# Relays.net
KiCad netlist of a schematic drawn in Altium Designer
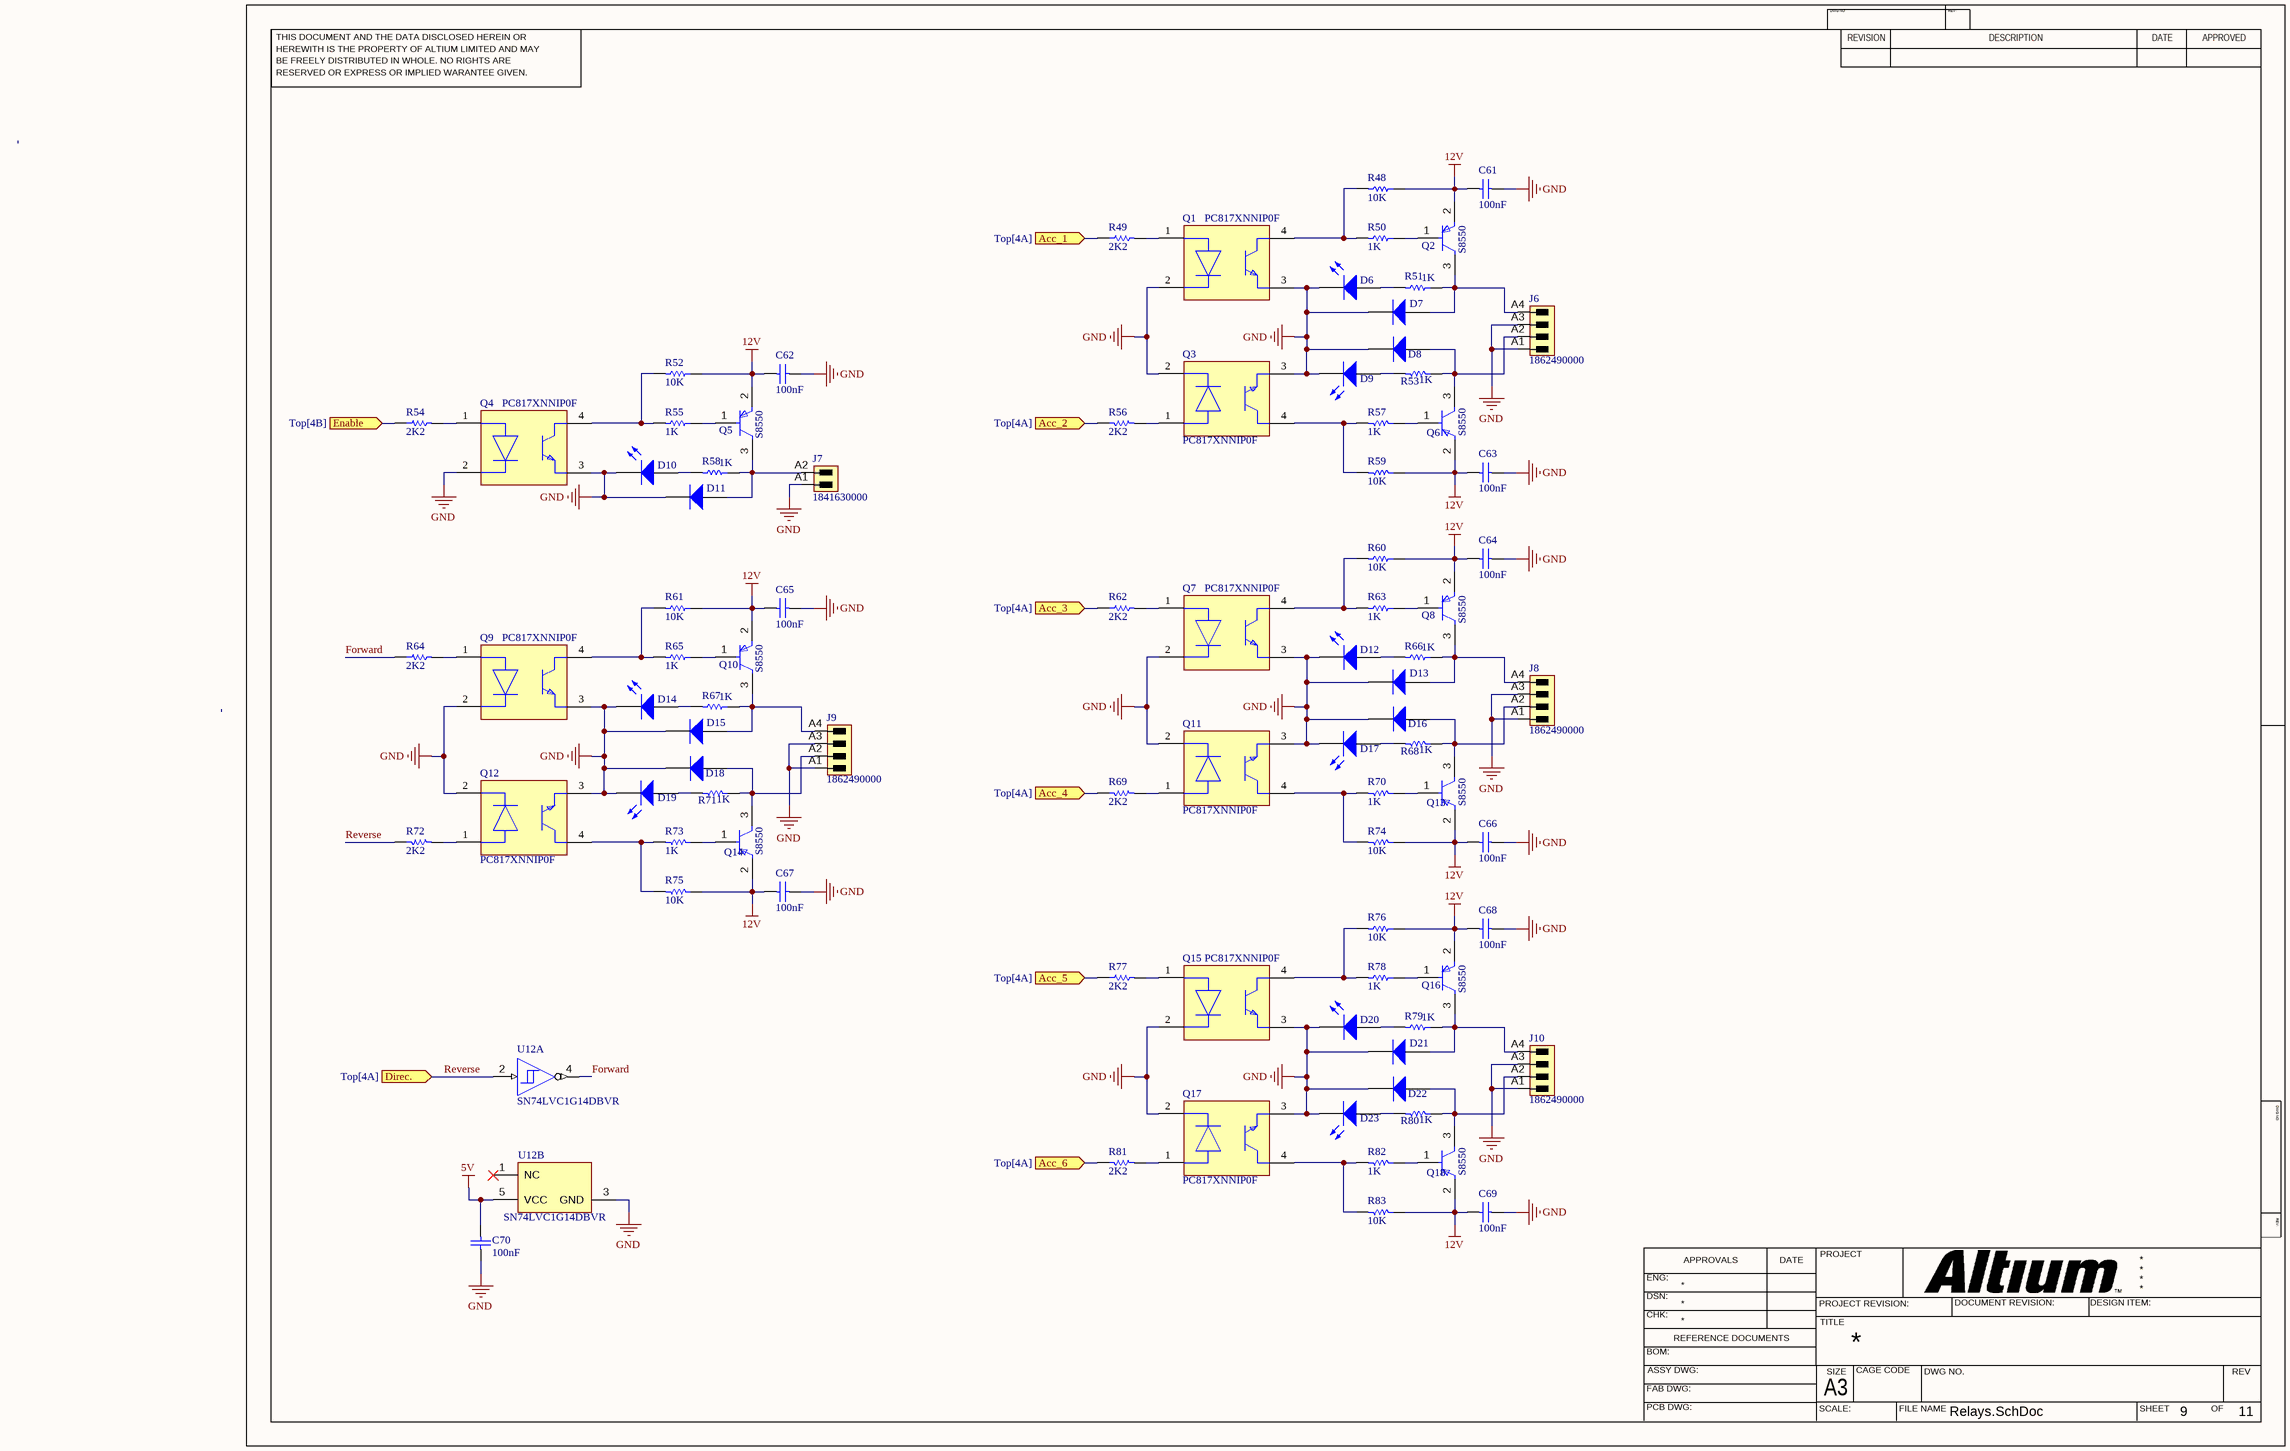
[diagram p0: Relays.SchDoc]

(export (version "E")
  (design (tool "Eeschema 10.0.6"))
  (components
    (comp (ref "C61")
      (value "100nF")
      (description "Capacitor")
      (libsource (lib "Simulation Generic Components") (part "Capacitor"))
    )
    (comp (ref "C62")
      (value "100nF")
      (description "Capacitor")
      (libsource (lib "Simulation Generic Components") (part "Capacitor"))
    )
    (comp (ref "C63")
      (value "100nF")
      (description "Capacitor")
      (libsource (lib "Simulation Generic Components") (part "Capacitor"))
    )
    (comp (ref "C64")
      (value "100nF")
      (description "Capacitor")
      (libsource (lib "Simulation Generic Components") (part "Capacitor"))
    )
    (comp (ref "C65")
      (value "100nF")
      (description "Capacitor")
      (libsource (lib "Simulation Generic Components") (part "Capacitor"))
    )
    (comp (ref "C66")
      (value "100nF")
      (description "Capacitor")
      (libsource (lib "Simulation Generic Components") (part "Capacitor"))
    )
    (comp (ref "C67")
      (value "100nF")
      (description "Capacitor")
      (libsource (lib "Simulation Generic Components") (part "Capacitor"))
    )
    (comp (ref "C68")
      (value "100nF")
      (description "Capacitor")
      (libsource (lib "Simulation Generic Components") (part "Capacitor"))
    )
    (comp (ref "C69")
      (value "100nF")
      (description "Capacitor")
      (libsource (lib "Simulation Generic Components") (part "Capacitor"))
    )
    (comp (ref "C70")
      (value "100nF")
      (description "Capacitor")
      (libsource (lib "Simulation Generic Components") (part "Capacitor"))
    )
    (comp (ref "D6")
      (value "Light-Emitting Diode")
      (libsource (lib "Simulation Generic Components") (part "LED"))
    )
    (comp (ref "D7") (value "Diode") (libsource (lib "Simulation Generic Components") (part "Diode")))
    (comp (ref "D8") (value "Diode") (libsource (lib "Simulation Generic Components") (part "Diode")))
    (comp (ref "D9")
      (value "Light-Emitting Diode")
      (libsource (lib "Simulation Generic Components") (part "LED"))
    )
    (comp (ref "D10")
      (value "Light-Emitting Diode")
      (libsource (lib "Simulation Generic Components") (part "LED"))
    )
    (comp (ref "D11") (value "Diode") (libsource (lib "Simulation Generic Components") (part "Diode")))
    (comp (ref "D12")
      (value "Light-Emitting Diode")
      (libsource (lib "Simulation Generic Components") (part "LED"))
    )
    (comp (ref "D13") (value "Diode") (libsource (lib "Simulation Generic Components") (part "Diode")))
    (comp (ref "D14")
      (value "Light-Emitting Diode")
      (libsource (lib "Simulation Generic Components") (part "LED"))
    )
    (comp (ref "D15") (value "Diode") (libsource (lib "Simulation Generic Components") (part "Diode")))
    (comp (ref "D16") (value "Diode") (libsource (lib "Simulation Generic Components") (part "Diode")))
    (comp (ref "D17")
      (value "Light-Emitting Diode")
      (libsource (lib "Simulation Generic Components") (part "LED"))
    )
    (comp (ref "D18") (value "Diode") (libsource (lib "Simulation Generic Components") (part "Diode")))
    (comp (ref "D19")
      (value "Light-Emitting Diode")
      (libsource (lib "Simulation Generic Components") (part "LED"))
    )
    (comp (ref "D20")
      (value "Light-Emitting Diode")
      (libsource (lib "Simulation Generic Components") (part "LED"))
    )
    (comp (ref "D21") (value "Diode") (libsource (lib "Simulation Generic Components") (part "Diode")))
    (comp (ref "D22") (value "Diode") (libsource (lib "Simulation Generic Components") (part "Diode")))
    (comp (ref "D23")
      (value "Light-Emitting Diode")
      (libsource (lib "Simulation Generic Components") (part "LED"))
    )
    (comp (ref "J6")
      (value "1862490000")
      (footprint "SC_SMT_3_81_90G_04")
      (description "OMNIMATE Signal - series BC/SC 3.81")
      (fields (field (name "MANUFACTURER") "Weidmueller"))
      (libsource (lib "Altium Content Vault") (part "Header_Male_04_1x04"))
    )
    (comp (ref "J7")
      (value "1841630000")
      (footprint "SL_SMT_3_5_90G_02")
      (description "OMNIMATE Signal - series BL/SL 3.50")
      (fields (field (name "MANUFACTURER") "Weidmueller"))
      (libsource (lib "Altium Content Vault") (part "Header_Male_02_1x02"))
    )
    (comp (ref "J8")
      (value "1862490000")
      (footprint "SC_SMT_3_81_90G_04")
      (description "OMNIMATE Signal - series BC/SC 3.81")
      (fields (field (name "MANUFACTURER") "Weidmueller"))
      (libsource (lib "Altium Content Vault") (part "Header_Male_04_1x04"))
    )
    (comp (ref "J9")
      (value "1862490000")
      (footprint "SC_SMT_3_81_90G_04")
      (description "OMNIMATE Signal - series BC/SC 3.81")
      (fields (field (name "MANUFACTURER") "Weidmueller"))
      (libsource (lib "Altium Content Vault") (part "Header_Male_04_1x04"))
    )
    (comp (ref "J10")
      (value "1862490000")
      (footprint "SC_SMT_3_81_90G_04")
      (description "OMNIMATE Signal - series BC/SC 3.81")
      (fields (field (name "MANUFACTURER") "Weidmueller"))
      (libsource (lib "Altium Content Vault") (part "Header_Male_04_1x04"))
    )
    (comp (ref "Q1")
      (value "PC817XNNIP0F")
      (footprint "FP-PC817XNNIP0F-MFG")
      (description "OPTOISOLATOR 5KV TRANS 4SMD")
      (libsource (lib "") (part "6470904bf6395c62928ee73e60120b8_1"))
    )
    (comp (ref "Q2")
      (value "S8550")
      (footprint "FP-SOT-23-IPC_B")
      (description "TRANS PNP 25V 1.5A SOT23")
      (libsource (lib "Altium Content Vault") (part "0e8486ed3b47d9c69b8404ba87cf0f7"))
    )
    (comp (ref "Q3")
      (value "PC817XNNIP0F")
      (footprint "FP-PC817XNNIP0F-MFG")
      (description "OPTOISOLATOR 5KV TRANS 4SMD")
      (libsource (lib "Altium Content Vault") (part "6470904bf6395c62928ee73e60120b8"))
    )
    (comp (ref "Q4")
      (value "PC817XNNIP0F")
      (footprint "FP-PC817XNNIP0F-MFG")
      (description "OPTOISOLATOR 5KV TRANS 4SMD")
      (libsource (lib "") (part "6470904bf6395c62928ee73e60120b8_1"))
    )
    (comp (ref "Q5")
      (value "S8550")
      (footprint "FP-SOT-23-IPC_B")
      (description "TRANS PNP 25V 1.5A SOT23")
      (libsource (lib "Altium Content Vault") (part "0e8486ed3b47d9c69b8404ba87cf0f7"))
    )
    (comp (ref "Q6")
      (value "S8550")
      (footprint "FP-SOT-23-IPC_B")
      (description "TRANS PNP 25V 1.5A SOT23")
      (libsource (lib "Altium Content Vault") (part "0e8486ed3b47d9c69b8404ba87cf0f7"))
    )
    (comp (ref "Q7")
      (value "PC817XNNIP0F")
      (footprint "FP-PC817XNNIP0F-MFG")
      (description "OPTOISOLATOR 5KV TRANS 4SMD")
      (libsource (lib "") (part "6470904bf6395c62928ee73e60120b8_1"))
    )
    (comp (ref "Q8")
      (value "S8550")
      (footprint "FP-SOT-23-IPC_B")
      (description "TRANS PNP 25V 1.5A SOT23")
      (libsource (lib "Altium Content Vault") (part "0e8486ed3b47d9c69b8404ba87cf0f7"))
    )
    (comp (ref "Q9")
      (value "PC817XNNIP0F")
      (footprint "FP-PC817XNNIP0F-MFG")
      (description "OPTOISOLATOR 5KV TRANS 4SMD")
      (libsource (lib "") (part "6470904bf6395c62928ee73e60120b8_1"))
    )
    (comp (ref "Q10")
      (value "S8550")
      (footprint "FP-SOT-23-IPC_B")
      (description "TRANS PNP 25V 1.5A SOT23")
      (libsource (lib "Altium Content Vault") (part "0e8486ed3b47d9c69b8404ba87cf0f7"))
    )
    (comp (ref "Q11")
      (value "PC817XNNIP0F")
      (footprint "FP-PC817XNNIP0F-MFG")
      (description "OPTOISOLATOR 5KV TRANS 4SMD")
      (libsource (lib "Altium Content Vault") (part "6470904bf6395c62928ee73e60120b8"))
    )
    (comp (ref "Q12")
      (value "PC817XNNIP0F")
      (footprint "FP-PC817XNNIP0F-MFG")
      (description "OPTOISOLATOR 5KV TRANS 4SMD")
      (libsource (lib "Altium Content Vault") (part "6470904bf6395c62928ee73e60120b8"))
    )
    (comp (ref "Q13")
      (value "S8550")
      (footprint "FP-SOT-23-IPC_B")
      (description "TRANS PNP 25V 1.5A SOT23")
      (libsource (lib "Altium Content Vault") (part "0e8486ed3b47d9c69b8404ba87cf0f7"))
    )
    (comp (ref "Q14")
      (value "S8550")
      (footprint "FP-SOT-23-IPC_B")
      (description "TRANS PNP 25V 1.5A SOT23")
      (libsource (lib "Altium Content Vault") (part "0e8486ed3b47d9c69b8404ba87cf0f7"))
    )
    (comp (ref "Q15")
      (value "PC817XNNIP0F")
      (footprint "FP-PC817XNNIP0F-MFG")
      (description "OPTOISOLATOR 5KV TRANS 4SMD")
      (libsource (lib "") (part "6470904bf6395c62928ee73e60120b8_1"))
    )
    (comp (ref "Q16")
      (value "S8550")
      (footprint "FP-SOT-23-IPC_B")
      (description "TRANS PNP 25V 1.5A SOT23")
      (libsource (lib "Altium Content Vault") (part "0e8486ed3b47d9c69b8404ba87cf0f7"))
    )
    (comp (ref "Q17")
      (value "PC817XNNIP0F")
      (footprint "FP-PC817XNNIP0F-MFG")
      (description "OPTOISOLATOR 5KV TRANS 4SMD")
      (libsource (lib "Altium Content Vault") (part "6470904bf6395c62928ee73e60120b8"))
    )
    (comp (ref "Q18")
      (value "S8550")
      (footprint "FP-SOT-23-IPC_B")
      (description "TRANS PNP 25V 1.5A SOT23")
      (libsource (lib "Altium Content Vault") (part "0e8486ed3b47d9c69b8404ba87cf0f7"))
    )
    (comp (ref "R48")
      (value "10K")
      (description "Resistor")
      (libsource (lib "Simulation Generic Components") (part "Resistor"))
    )
    (comp (ref "R49")
      (value "2K2")
      (description "Resistor")
      (libsource (lib "Simulation Generic Components") (part "Resistor"))
    )
    (comp (ref "R50")
      (value "1K")
      (description "Resistor")
      (libsource (lib "Simulation Generic Components") (part "Resistor"))
    )
    (comp (ref "R51")
      (value "1K")
      (description "Resistor")
      (libsource (lib "Simulation Generic Components") (part "Resistor"))
    )
    (comp (ref "R52")
      (value "10K")
      (description "Resistor")
      (libsource (lib "Simulation Generic Components") (part "Resistor"))
    )
    (comp (ref "R53")
      (value "1K")
      (description "Resistor")
      (libsource (lib "Simulation Generic Components") (part "Resistor"))
    )
    (comp (ref "R54")
      (value "2K2")
      (description "Resistor")
      (libsource (lib "Simulation Generic Components") (part "Resistor"))
    )
    (comp (ref "R55")
      (value "1K")
      (description "Resistor")
      (libsource (lib "Simulation Generic Components") (part "Resistor"))
    )
    (comp (ref "R56")
      (value "2K2")
      (description "Resistor")
      (libsource (lib "Simulation Generic Components") (part "Resistor"))
    )
    (comp (ref "R57")
      (value "1K")
      (description "Resistor")
      (libsource (lib "Simulation Generic Components") (part "Resistor"))
    )
    (comp (ref "R58")
      (value "1K")
      (description "Resistor")
      (libsource (lib "Simulation Generic Components") (part "Resistor"))
    )
    (comp (ref "R59")
      (value "10K")
      (description "Resistor")
      (libsource (lib "Simulation Generic Components") (part "Resistor"))
    )
    (comp (ref "R60")
      (value "10K")
      (description "Resistor")
      (libsource (lib "Simulation Generic Components") (part "Resistor"))
    )
    (comp (ref "R61")
      (value "10K")
      (description "Resistor")
      (libsource (lib "Simulation Generic Components") (part "Resistor"))
    )
    (comp (ref "R62")
      (value "2K2")
      (description "Resistor")
      (libsource (lib "Simulation Generic Components") (part "Resistor"))
    )
    (comp (ref "R63")
      (value "1K")
      (description "Resistor")
      (libsource (lib "Simulation Generic Components") (part "Resistor"))
    )
    (comp (ref "R64")
      (value "2K2")
      (description "Resistor")
      (libsource (lib "Simulation Generic Components") (part "Resistor"))
    )
    (comp (ref "R65")
      (value "1K")
      (description "Resistor")
      (libsource (lib "Simulation Generic Components") (part "Resistor"))
    )
    (comp (ref "R66")
      (value "1K")
      (description "Resistor")
      (libsource (lib "Simulation Generic Components") (part "Resistor"))
    )
    (comp (ref "R67")
      (value "1K")
      (description "Resistor")
      (libsource (lib "Simulation Generic Components") (part "Resistor"))
    )
    (comp (ref "R68")
      (value "1K")
      (description "Resistor")
      (libsource (lib "Simulation Generic Components") (part "Resistor"))
    )
    (comp (ref "R69")
      (value "2K2")
      (description "Resistor")
      (libsource (lib "Simulation Generic Components") (part "Resistor"))
    )
    (comp (ref "R70")
      (value "1K")
      (description "Resistor")
      (libsource (lib "Simulation Generic Components") (part "Resistor"))
    )
    (comp (ref "R71")
      (value "1K")
      (description "Resistor")
      (libsource (lib "Simulation Generic Components") (part "Resistor"))
    )
    (comp (ref "R72")
      (value "2K2")
      (description "Resistor")
      (libsource (lib "Simulation Generic Components") (part "Resistor"))
    )
    (comp (ref "R73")
      (value "1K")
      (description "Resistor")
      (libsource (lib "Simulation Generic Components") (part "Resistor"))
    )
    (comp (ref "R74")
      (value "10K")
      (description "Resistor")
      (libsource (lib "Simulation Generic Components") (part "Resistor"))
    )
    (comp (ref "R75")
      (value "10K")
      (description "Resistor")
      (libsource (lib "Simulation Generic Components") (part "Resistor"))
    )
    (comp (ref "R76")
      (value "10K")
      (description "Resistor")
      (libsource (lib "Simulation Generic Components") (part "Resistor"))
    )
    (comp (ref "R77")
      (value "2K2")
      (description "Resistor")
      (libsource (lib "Simulation Generic Components") (part "Resistor"))
    )
    (comp (ref "R78")
      (value "1K")
      (description "Resistor")
      (libsource (lib "Simulation Generic Components") (part "Resistor"))
    )
    (comp (ref "R79")
      (value "1K")
      (description "Resistor")
      (libsource (lib "Simulation Generic Components") (part "Resistor"))
    )
    (comp (ref "R80")
      (value "1K")
      (description "Resistor")
      (libsource (lib "Simulation Generic Components") (part "Resistor"))
    )
    (comp (ref "R81")
      (value "2K2")
      (description "Resistor")
      (libsource (lib "Simulation Generic Components") (part "Resistor"))
    )
    (comp (ref "R82")
      (value "1K")
      (description "Resistor")
      (libsource (lib "Simulation Generic Components") (part "Resistor"))
    )
    (comp (ref "R83")
      (value "10K")
      (description "Resistor")
      (libsource (lib "Simulation Generic Components") (part "Resistor"))
    )
    (comp (ref "U12")
      (value "SN74LVC1G14DBVR")
      (footprint "DBV0005A_L")
      (description "Single Schmitt-Trigger Inverter, DBV0005A, LARGE T&R")
      (fields
        (field (name "GENERIC PART NUMBER") "SN74LVC1G14")
        (field (name "MANUFACTURER") "Texas Instruments")
      )
      (libsource (lib "Altium Content Vault") (part "TI-SN74XXX1XX4-XX-5-SCHMITT"))
    )
  )
  (nets
    (net (code "1") (name "/Acc_1") (class "Default")
      (node (ref "R49") (pin "1") (pinfunction "1_1") (pintype "passive"))
    )
    (net (code "2") (name "/Acc_2") (class "Default")
      (node (ref "R56") (pin "1") (pinfunction "1_1") (pintype "passive"))
    )
    (net (code "3") (name "/Acc_3") (class "Default")
      (node (ref "R62") (pin "1") (pinfunction "1_1") (pintype "passive"))
    )
    (net (code "4") (name "/Acc_4") (class "Default")
      (node (ref "R69") (pin "1") (pinfunction "1_1") (pintype "passive"))
    )
    (net (code "5") (name "/Acc_5") (class "Default")
      (node (ref "R77") (pin "1") (pinfunction "1_1") (pintype "passive"))
    )
    (net (code "6") (name "/Acc_6") (class "Default")
      (node (ref "R81") (pin "1") (pinfunction "1_1") (pintype "passive"))
    )
    (net (code "7") (name "/Enable") (class "Default")
      (node (ref "R54") (pin "1") (pinfunction "1_1") (pintype "passive"))
    )
    (net (code "8") (name "/Forward") (class "Default")
      (node (ref "R64") (pin "1") (pinfunction "1_1") (pintype "passive"))
      (node (ref "U12") (pin "4") (pinfunction "Y_4") (pintype "output"))
    )
    (net (code "9") (name "/Reverse") (class "Default")
      (node (ref "R72") (pin "1") (pinfunction "1_1") (pintype "passive"))
      (node (ref "U12") (pin "2") (pinfunction "A_2") (pintype "input"))
    )
    (net (code "10") (name "5V") (class "Default")
      (node (ref "C70") (pin "1") (pinfunction "1_1") (pintype "passive"))
      (node (ref "U12") (pin "5") (pinfunction "VCC_5") (pintype "power_in"))
    )
    (net (code "11") (name "12V") (class "Default")
      (node (ref "C61") (pin "1") (pinfunction "1_1") (pintype "passive"))
      (node (ref "C62") (pin "1") (pinfunction "1_1") (pintype "passive"))
      (node (ref "C63") (pin "1") (pinfunction "1_1") (pintype "passive"))
      (node (ref "C64") (pin "1") (pinfunction "1_1") (pintype "passive"))
      (node (ref "C65") (pin "1") (pinfunction "1_1") (pintype "passive"))
      (node (ref "C66") (pin "1") (pinfunction "1_1") (pintype "passive"))
      (node (ref "C67") (pin "1") (pinfunction "1_1") (pintype "passive"))
      (node (ref "C68") (pin "1") (pinfunction "1_1") (pintype "passive"))
      (node (ref "C69") (pin "1") (pinfunction "1_1") (pintype "passive"))
      (node (ref "Q10") (pin "2") (pinfunction "E_2") (pintype "passive"))
      (node (ref "Q13") (pin "2") (pinfunction "E_2") (pintype "passive"))
      (node (ref "Q14") (pin "2") (pinfunction "E_2") (pintype "passive"))
      (node (ref "Q16") (pin "2") (pinfunction "E_2") (pintype "passive"))
      (node (ref "Q18") (pin "2") (pinfunction "E_2") (pintype "passive"))
      (node (ref "Q2") (pin "2") (pinfunction "E_2") (pintype "passive"))
      (node (ref "Q5") (pin "2") (pinfunction "E_2") (pintype "passive"))
      (node (ref "Q6") (pin "2") (pinfunction "E_2") (pintype "passive"))
      (node (ref "Q8") (pin "2") (pinfunction "E_2") (pintype "passive"))
      (node (ref "R48") (pin "1") (pinfunction "1_1") (pintype "passive"))
      (node (ref "R52") (pin "1") (pinfunction "1_1") (pintype "passive"))
      (node (ref "R59") (pin "1") (pinfunction "1_1") (pintype "passive"))
      (node (ref "R60") (pin "1") (pinfunction "1_1") (pintype "passive"))
      (node (ref "R61") (pin "1") (pinfunction "1_1") (pintype "passive"))
      (node (ref "R74") (pin "1") (pinfunction "1_1") (pintype "passive"))
      (node (ref "R75") (pin "1") (pinfunction "1_1") (pintype "passive"))
      (node (ref "R76") (pin "1") (pinfunction "1_1") (pintype "passive"))
      (node (ref "R83") (pin "1") (pinfunction "1_1") (pintype "passive"))
    )
    (net (code "12") (name "GND") (class "Default")
      (node (ref "C61") (pin "2") (pinfunction "2_2") (pintype "passive"))
      (node (ref "C62") (pin "2") (pinfunction "2_2") (pintype "passive"))
      (node (ref "C63") (pin "2") (pinfunction "2_2") (pintype "passive"))
      (node (ref "C64") (pin "2") (pinfunction "2_2") (pintype "passive"))
      (node (ref "C65") (pin "2") (pinfunction "2_2") (pintype "passive"))
      (node (ref "C66") (pin "2") (pinfunction "2_2") (pintype "passive"))
      (node (ref "C67") (pin "2") (pinfunction "2_2") (pintype "passive"))
      (node (ref "C68") (pin "2") (pinfunction "2_2") (pintype "passive"))
      (node (ref "C69") (pin "2") (pinfunction "2_2") (pintype "passive"))
      (node (ref "C70") (pin "2") (pinfunction "2_2") (pintype "passive"))
      (node (ref "D10") (pin "2") (pinfunction "K_2") (pintype "passive"))
      (node (ref "D11") (pin "2") (pinfunction "K_2") (pintype "passive"))
      (node (ref "D12") (pin "2") (pinfunction "K_2") (pintype "passive"))
      (node (ref "D13") (pin "2") (pinfunction "K_2") (pintype "passive"))
      (node (ref "D14") (pin "2") (pinfunction "K_2") (pintype "passive"))
      (node (ref "D15") (pin "2") (pinfunction "K_2") (pintype "passive"))
      (node (ref "D16") (pin "2") (pinfunction "K_2") (pintype "passive"))
      (node (ref "D17") (pin "2") (pinfunction "K_2") (pintype "passive"))
      (node (ref "D18") (pin "2") (pinfunction "K_2") (pintype "passive"))
      (node (ref "D19") (pin "2") (pinfunction "K_2") (pintype "passive"))
      (node (ref "D20") (pin "2") (pinfunction "K_2") (pintype "passive"))
      (node (ref "D21") (pin "2") (pinfunction "K_2") (pintype "passive"))
      (node (ref "D22") (pin "2") (pinfunction "K_2") (pintype "passive"))
      (node (ref "D23") (pin "2") (pinfunction "K_2") (pintype "passive"))
      (node (ref "D6") (pin "2") (pinfunction "K_2") (pintype "passive"))
      (node (ref "D7") (pin "2") (pinfunction "K_2") (pintype "passive"))
      (node (ref "D8") (pin "2") (pinfunction "K_2") (pintype "passive"))
      (node (ref "D9") (pin "2") (pinfunction "K_2") (pintype "passive"))
      (node (ref "J10") (pin "A1") (pinfunction "A1_A1") (pintype "passive"))
      (node (ref "J10") (pin "A3") (pinfunction "A3_A3") (pintype "passive"))
      (node (ref "J6") (pin "A1") (pinfunction "A1_A1") (pintype "passive"))
      (node (ref "J6") (pin "A3") (pinfunction "A3_A3") (pintype "passive"))
      (node (ref "J7") (pin "A1") (pinfunction "A1_A1") (pintype "passive"))
      (node (ref "J8") (pin "A1") (pinfunction "A1_A1") (pintype "passive"))
      (node (ref "J8") (pin "A3") (pinfunction "A3_A3") (pintype "passive"))
      (node (ref "J9") (pin "A1") (pinfunction "A1_A1") (pintype "passive"))
      (node (ref "J9") (pin "A3") (pinfunction "A3_A3") (pintype "passive"))
      (node (ref "Q1") (pin "2") (pinfunction "C_2") (pintype "passive"))
      (node (ref "Q1") (pin "3") (pinfunction "E_3") (pintype "passive"))
      (node (ref "Q11") (pin "2") (pinfunction "C_2") (pintype "passive"))
      (node (ref "Q11") (pin "3") (pinfunction "E_3") (pintype "passive"))
      (node (ref "Q12") (pin "2") (pinfunction "C_2") (pintype "passive"))
      (node (ref "Q12") (pin "3") (pinfunction "E_3") (pintype "passive"))
      (node (ref "Q15") (pin "2") (pinfunction "C_2") (pintype "passive"))
      (node (ref "Q15") (pin "3") (pinfunction "E_3") (pintype "passive"))
      (node (ref "Q17") (pin "2") (pinfunction "C_2") (pintype "passive"))
      (node (ref "Q17") (pin "3") (pinfunction "E_3") (pintype "passive"))
      (node (ref "Q3") (pin "2") (pinfunction "C_2") (pintype "passive"))
      (node (ref "Q3") (pin "3") (pinfunction "E_3") (pintype "passive"))
      (node (ref "Q4") (pin "2") (pinfunction "C_2") (pintype "passive"))
      (node (ref "Q4") (pin "3") (pinfunction "E_3") (pintype "passive"))
      (node (ref "Q7") (pin "2") (pinfunction "C_2") (pintype "passive"))
      (node (ref "Q7") (pin "3") (pinfunction "E_3") (pintype "passive"))
      (node (ref "Q9") (pin "2") (pinfunction "C_2") (pintype "passive"))
      (node (ref "Q9") (pin "3") (pinfunction "E_3") (pintype "passive"))
      (node (ref "U12") (pin "3") (pinfunction "GND_3") (pintype "power_in"))
    )
    (net (code "13") (name "Net-(D6-A)") (class "Default")
      (node (ref "D6") (pin "1") (pinfunction "A_1") (pintype "passive"))
      (node (ref "R51") (pin "2") (pinfunction "2_2") (pintype "passive"))
    )
    (net (code "14") (name "Net-(D7-A)") (class "Default")
      (node (ref "D7") (pin "1") (pinfunction "A_1") (pintype "passive"))
      (node (ref "J6") (pin "A4") (pinfunction "A4_A4") (pintype "passive"))
      (node (ref "Q2") (pin "3") (pinfunction "C_3") (pintype "passive"))
      (node (ref "R51") (pin "1") (pinfunction "1_1") (pintype "passive"))
    )
    (net (code "15") (name "Net-(D8-A)") (class "Default")
      (node (ref "D8") (pin "1") (pinfunction "A_1") (pintype "passive"))
      (node (ref "J6") (pin "A2") (pinfunction "A2_A2") (pintype "passive"))
      (node (ref "Q6") (pin "3") (pinfunction "C_3") (pintype "passive"))
      (node (ref "R53") (pin "1") (pinfunction "1_1") (pintype "passive"))
    )
    (net (code "16") (name "Net-(D9-A)") (class "Default")
      (node (ref "D9") (pin "1") (pinfunction "A_1") (pintype "passive"))
      (node (ref "R53") (pin "2") (pinfunction "2_2") (pintype "passive"))
    )
    (net (code "17") (name "Net-(D10-A)") (class "Default")
      (node (ref "D10") (pin "1") (pinfunction "A_1") (pintype "passive"))
      (node (ref "R58") (pin "2") (pinfunction "2_2") (pintype "passive"))
    )
    (net (code "18") (name "Net-(D11-A)") (class "Default")
      (node (ref "D11") (pin "1") (pinfunction "A_1") (pintype "passive"))
      (node (ref "J7") (pin "A2") (pinfunction "A2_A2") (pintype "passive"))
      (node (ref "Q5") (pin "3") (pinfunction "C_3") (pintype "passive"))
      (node (ref "R58") (pin "1") (pinfunction "1_1") (pintype "passive"))
    )
    (net (code "19") (name "Net-(D12-A)") (class "Default")
      (node (ref "D12") (pin "1") (pinfunction "A_1") (pintype "passive"))
      (node (ref "R66") (pin "2") (pinfunction "2_2") (pintype "passive"))
    )
    (net (code "20") (name "Net-(D13-A)") (class "Default")
      (node (ref "D13") (pin "1") (pinfunction "A_1") (pintype "passive"))
      (node (ref "J8") (pin "A4") (pinfunction "A4_A4") (pintype "passive"))
      (node (ref "Q8") (pin "3") (pinfunction "C_3") (pintype "passive"))
      (node (ref "R66") (pin "1") (pinfunction "1_1") (pintype "passive"))
    )
    (net (code "21") (name "Net-(D14-A)") (class "Default")
      (node (ref "D14") (pin "1") (pinfunction "A_1") (pintype "passive"))
      (node (ref "R67") (pin "2") (pinfunction "2_2") (pintype "passive"))
    )
    (net (code "22") (name "Net-(D15-A)") (class "Default")
      (node (ref "D15") (pin "1") (pinfunction "A_1") (pintype "passive"))
      (node (ref "J9") (pin "A4") (pinfunction "A4_A4") (pintype "passive"))
      (node (ref "Q10") (pin "3") (pinfunction "C_3") (pintype "passive"))
      (node (ref "R67") (pin "1") (pinfunction "1_1") (pintype "passive"))
    )
    (net (code "23") (name "Net-(D16-A)") (class "Default")
      (node (ref "D16") (pin "1") (pinfunction "A_1") (pintype "passive"))
      (node (ref "J8") (pin "A2") (pinfunction "A2_A2") (pintype "passive"))
      (node (ref "Q13") (pin "3") (pinfunction "C_3") (pintype "passive"))
      (node (ref "R68") (pin "1") (pinfunction "1_1") (pintype "passive"))
    )
    (net (code "24") (name "Net-(D17-A)") (class "Default")
      (node (ref "D17") (pin "1") (pinfunction "A_1") (pintype "passive"))
      (node (ref "R68") (pin "2") (pinfunction "2_2") (pintype "passive"))
    )
    (net (code "25") (name "Net-(D18-A)") (class "Default")
      (node (ref "D18") (pin "1") (pinfunction "A_1") (pintype "passive"))
      (node (ref "J9") (pin "A2") (pinfunction "A2_A2") (pintype "passive"))
      (node (ref "Q14") (pin "3") (pinfunction "C_3") (pintype "passive"))
      (node (ref "R71") (pin "1") (pinfunction "1_1") (pintype "passive"))
    )
    (net (code "26") (name "Net-(D19-A)") (class "Default")
      (node (ref "D19") (pin "1") (pinfunction "A_1") (pintype "passive"))
      (node (ref "R71") (pin "2") (pinfunction "2_2") (pintype "passive"))
    )
    (net (code "27") (name "Net-(D20-A)") (class "Default")
      (node (ref "D20") (pin "1") (pinfunction "A_1") (pintype "passive"))
      (node (ref "R79") (pin "2") (pinfunction "2_2") (pintype "passive"))
    )
    (net (code "28") (name "Net-(D21-A)") (class "Default")
      (node (ref "D21") (pin "1") (pinfunction "A_1") (pintype "passive"))
      (node (ref "J10") (pin "A4") (pinfunction "A4_A4") (pintype "passive"))
      (node (ref "Q16") (pin "3") (pinfunction "C_3") (pintype "passive"))
      (node (ref "R79") (pin "1") (pinfunction "1_1") (pintype "passive"))
    )
    (net (code "29") (name "Net-(D22-A)") (class "Default")
      (node (ref "D22") (pin "1") (pinfunction "A_1") (pintype "passive"))
      (node (ref "J10") (pin "A2") (pinfunction "A2_A2") (pintype "passive"))
      (node (ref "Q18") (pin "3") (pinfunction "C_3") (pintype "passive"))
      (node (ref "R80") (pin "1") (pinfunction "1_1") (pintype "passive"))
    )
    (net (code "30") (name "Net-(D23-A)") (class "Default")
      (node (ref "D23") (pin "1") (pinfunction "A_1") (pintype "passive"))
      (node (ref "R80") (pin "2") (pinfunction "2_2") (pintype "passive"))
    )
    (net (code "31") (name "Net-(Q1-A)") (class "Default")
      (node (ref "Q1") (pin "1") (pinfunction "A_1") (pintype "passive"))
      (node (ref "R49") (pin "2") (pinfunction "2_2") (pintype "passive"))
    )
    (net (code "32") (name "Net-(Q1-C-Pad4)") (class "Default")
      (node (ref "Q1") (pin "4") (pinfunction "C_4") (pintype "passive"))
      (node (ref "R48") (pin "2") (pinfunction "2_2") (pintype "passive"))
      (node (ref "R50") (pin "2") (pinfunction "2_2") (pintype "passive"))
    )
    (net (code "33") (name "Net-(Q2-B)") (class "Default")
      (node (ref "Q2") (pin "1") (pinfunction "B_1") (pintype "passive"))
      (node (ref "R50") (pin "1") (pinfunction "1_1") (pintype "passive"))
    )
    (net (code "34") (name "Net-(Q3-A)") (class "Default")
      (node (ref "Q3") (pin "1") (pinfunction "A_1") (pintype "passive"))
      (node (ref "R56") (pin "2") (pinfunction "2_2") (pintype "passive"))
    )
    (net (code "35") (name "Net-(Q3-C-Pad4)") (class "Default")
      (node (ref "Q3") (pin "4") (pinfunction "C_4") (pintype "passive"))
      (node (ref "R57") (pin "2") (pinfunction "2_2") (pintype "passive"))
      (node (ref "R59") (pin "2") (pinfunction "2_2") (pintype "passive"))
    )
    (net (code "36") (name "Net-(Q4-A)") (class "Default")
      (node (ref "Q4") (pin "1") (pinfunction "A_1") (pintype "passive"))
      (node (ref "R54") (pin "2") (pinfunction "2_2") (pintype "passive"))
    )
    (net (code "37") (name "Net-(Q4-C-Pad4)") (class "Default")
      (node (ref "Q4") (pin "4") (pinfunction "C_4") (pintype "passive"))
      (node (ref "R52") (pin "2") (pinfunction "2_2") (pintype "passive"))
      (node (ref "R55") (pin "2") (pinfunction "2_2") (pintype "passive"))
    )
    (net (code "38") (name "Net-(Q5-B)") (class "Default")
      (node (ref "Q5") (pin "1") (pinfunction "B_1") (pintype "passive"))
      (node (ref "R55") (pin "1") (pinfunction "1_1") (pintype "passive"))
    )
    (net (code "39") (name "Net-(Q6-B)") (class "Default")
      (node (ref "Q6") (pin "1") (pinfunction "B_1") (pintype "passive"))
      (node (ref "R57") (pin "1") (pinfunction "1_1") (pintype "passive"))
    )
    (net (code "40") (name "Net-(Q7-A)") (class "Default")
      (node (ref "Q7") (pin "1") (pinfunction "A_1") (pintype "passive"))
      (node (ref "R62") (pin "2") (pinfunction "2_2") (pintype "passive"))
    )
    (net (code "41") (name "Net-(Q7-C-Pad4)") (class "Default")
      (node (ref "Q7") (pin "4") (pinfunction "C_4") (pintype "passive"))
      (node (ref "R60") (pin "2") (pinfunction "2_2") (pintype "passive"))
      (node (ref "R63") (pin "2") (pinfunction "2_2") (pintype "passive"))
    )
    (net (code "42") (name "Net-(Q8-B)") (class "Default")
      (node (ref "Q8") (pin "1") (pinfunction "B_1") (pintype "passive"))
      (node (ref "R63") (pin "1") (pinfunction "1_1") (pintype "passive"))
    )
    (net (code "43") (name "Net-(Q9-A)") (class "Default")
      (node (ref "Q9") (pin "1") (pinfunction "A_1") (pintype "passive"))
      (node (ref "R64") (pin "2") (pinfunction "2_2") (pintype "passive"))
    )
    (net (code "44") (name "Net-(Q9-C-Pad4)") (class "Default")
      (node (ref "Q9") (pin "4") (pinfunction "C_4") (pintype "passive"))
      (node (ref "R61") (pin "2") (pinfunction "2_2") (pintype "passive"))
      (node (ref "R65") (pin "2") (pinfunction "2_2") (pintype "passive"))
    )
    (net (code "45") (name "Net-(Q10-B)") (class "Default")
      (node (ref "Q10") (pin "1") (pinfunction "B_1") (pintype "passive"))
      (node (ref "R65") (pin "1") (pinfunction "1_1") (pintype "passive"))
    )
    (net (code "46") (name "Net-(Q11-A)") (class "Default")
      (node (ref "Q11") (pin "1") (pinfunction "A_1") (pintype "passive"))
      (node (ref "R69") (pin "2") (pinfunction "2_2") (pintype "passive"))
    )
    (net (code "47") (name "Net-(Q11-C-Pad4)") (class "Default")
      (node (ref "Q11") (pin "4") (pinfunction "C_4") (pintype "passive"))
      (node (ref "R70") (pin "2") (pinfunction "2_2") (pintype "passive"))
      (node (ref "R74") (pin "2") (pinfunction "2_2") (pintype "passive"))
    )
    (net (code "48") (name "Net-(Q12-A)") (class "Default")
      (node (ref "Q12") (pin "1") (pinfunction "A_1") (pintype "passive"))
      (node (ref "R72") (pin "2") (pinfunction "2_2") (pintype "passive"))
    )
    (net (code "49") (name "Net-(Q12-C-Pad4)") (class "Default")
      (node (ref "Q12") (pin "4") (pinfunction "C_4") (pintype "passive"))
      (node (ref "R73") (pin "2") (pinfunction "2_2") (pintype "passive"))
      (node (ref "R75") (pin "2") (pinfunction "2_2") (pintype "passive"))
    )
    (net (code "50") (name "Net-(Q13-B)") (class "Default")
      (node (ref "Q13") (pin "1") (pinfunction "B_1") (pintype "passive"))
      (node (ref "R70") (pin "1") (pinfunction "1_1") (pintype "passive"))
    )
    (net (code "51") (name "Net-(Q14-B)") (class "Default")
      (node (ref "Q14") (pin "1") (pinfunction "B_1") (pintype "passive"))
      (node (ref "R73") (pin "1") (pinfunction "1_1") (pintype "passive"))
    )
    (net (code "52") (name "Net-(Q15-A)") (class "Default")
      (node (ref "Q15") (pin "1") (pinfunction "A_1") (pintype "passive"))
      (node (ref "R77") (pin "2") (pinfunction "2_2") (pintype "passive"))
    )
    (net (code "53") (name "Net-(Q15-C-Pad4)") (class "Default")
      (node (ref "Q15") (pin "4") (pinfunction "C_4") (pintype "passive"))
      (node (ref "R76") (pin "2") (pinfunction "2_2") (pintype "passive"))
      (node (ref "R78") (pin "2") (pinfunction "2_2") (pintype "passive"))
    )
    (net (code "54") (name "Net-(Q16-B)") (class "Default")
      (node (ref "Q16") (pin "1") (pinfunction "B_1") (pintype "passive"))
      (node (ref "R78") (pin "1") (pinfunction "1_1") (pintype "passive"))
    )
    (net (code "55") (name "Net-(Q17-A)") (class "Default")
      (node (ref "Q17") (pin "1") (pinfunction "A_1") (pintype "passive"))
      (node (ref "R81") (pin "2") (pinfunction "2_2") (pintype "passive"))
    )
    (net (code "56") (name "Net-(Q17-C-Pad4)") (class "Default")
      (node (ref "Q17") (pin "4") (pinfunction "C_4") (pintype "passive"))
      (node (ref "R82") (pin "2") (pinfunction "2_2") (pintype "passive"))
      (node (ref "R83") (pin "2") (pinfunction "2_2") (pintype "passive"))
    )
    (net (code "57") (name "Net-(Q18-B)") (class "Default")
      (node (ref "Q18") (pin "1") (pinfunction "B_1") (pintype "passive"))
      (node (ref "R82") (pin "1") (pinfunction "1_1") (pintype "passive"))
    )
    (net (code "58") (name "unconnected-(U12B-NC-Pad1)") (class "Default")
      (node (ref "U12") (pin "1") (pinfunction "NC_1") (pintype "passive+no_connect"))
    )
  )
)
